# mbed_RevB.net
KiCad netlist of a schematic drawn in EAGLE
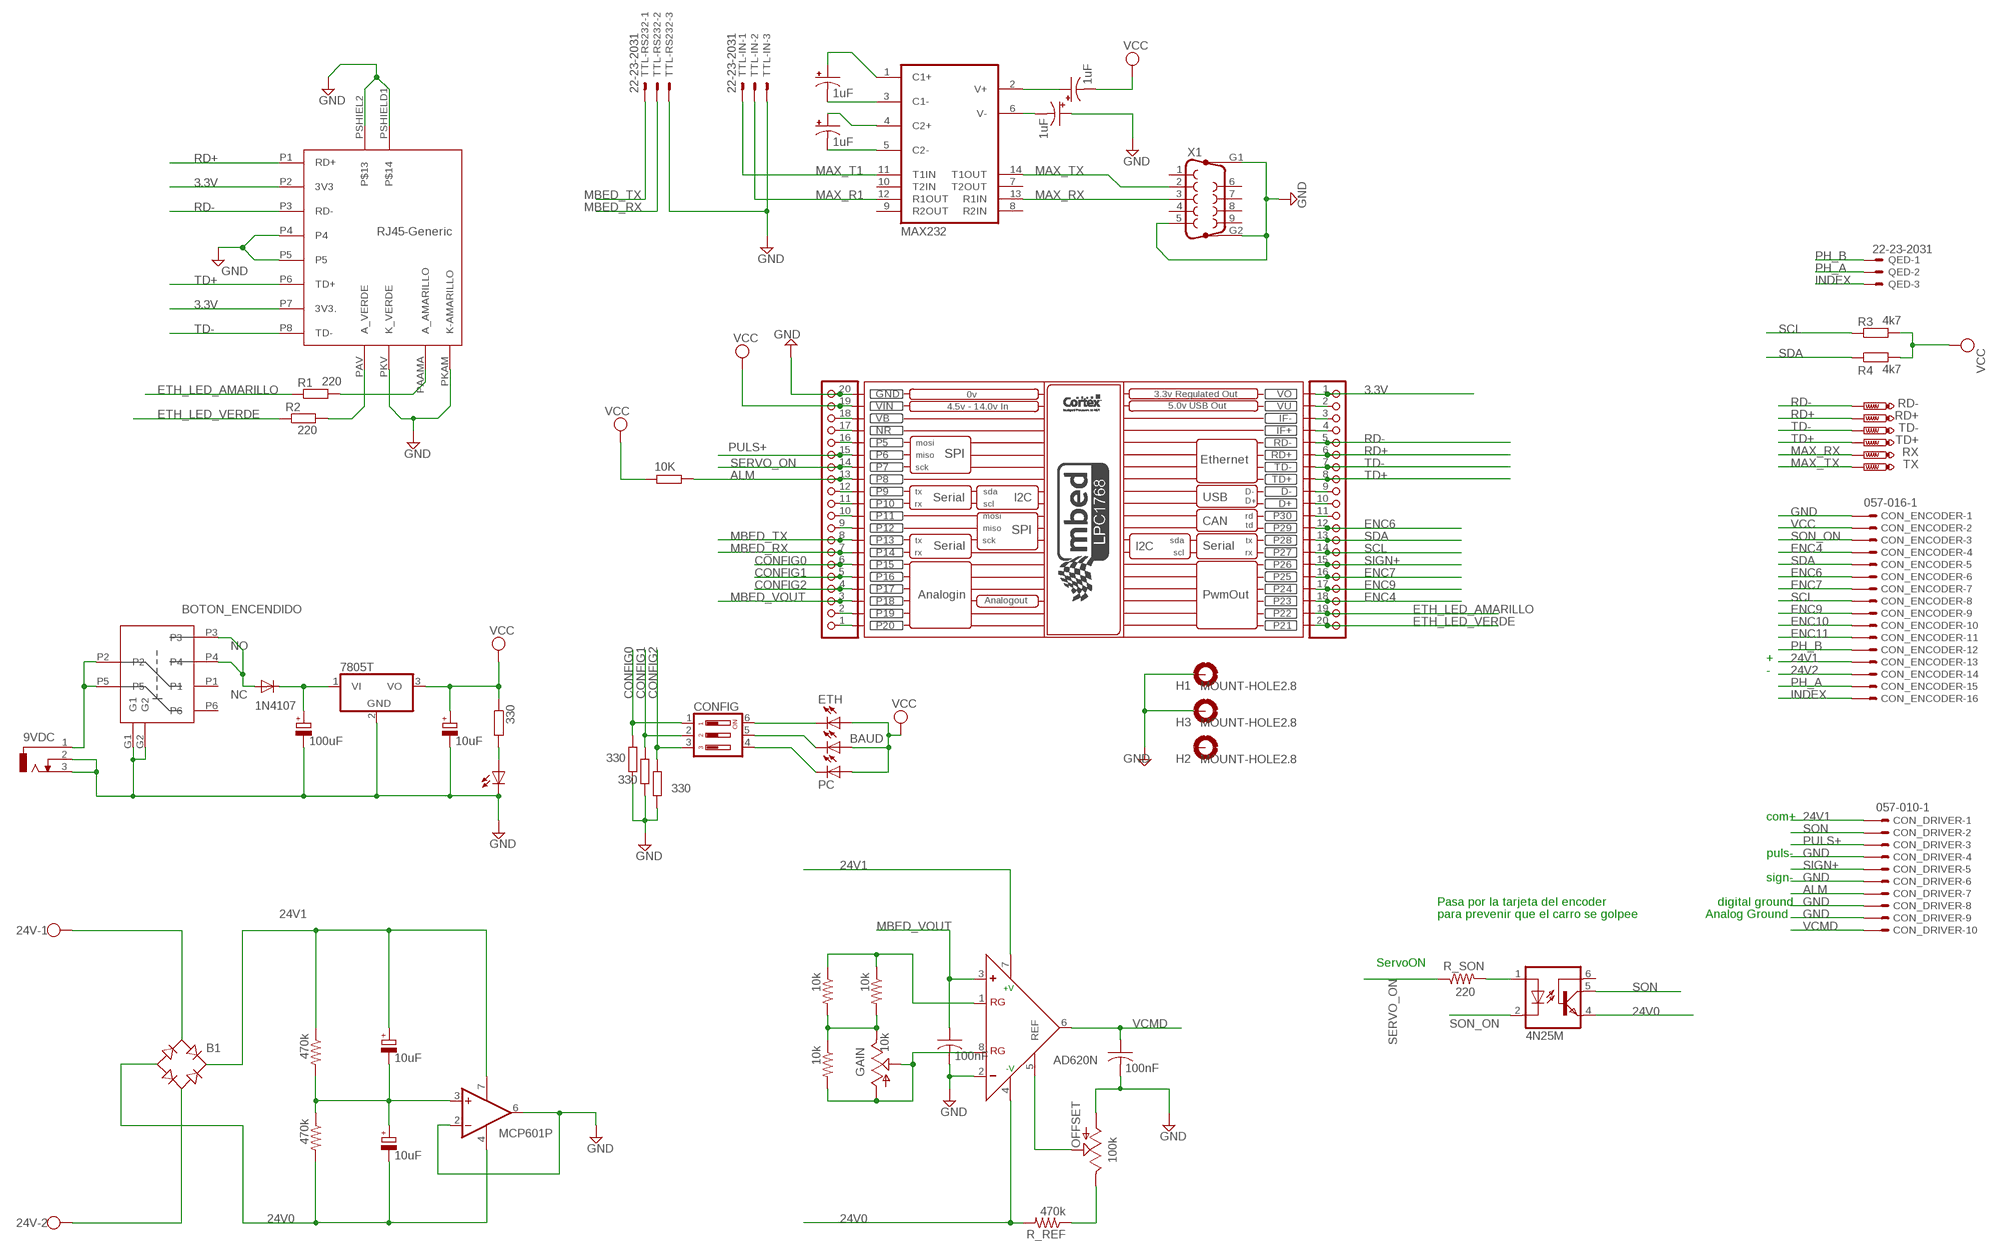
[diagram p0: schematic, sheet 1]

(export (version "E")
  (design (tool "Eeschema 10.0.6"))
  (components
    (comp (ref "9VDC")
      (value "DCJ0303")
      (footprint "eagle-import:DCJ0303")
      (libsource (lib "eagle-import") (part "DCJ0303"))
    )
    (comp (ref "24V")
      (value "W237-02P")
      (footprint "eagle-import:W237-132")
      (libsource (lib "eagle-import") (part "W237-02P"))
    )
    (comp (ref "B1")
      (value "RB1A")
      (footprint "eagle-import:RB1A")
      (libsource (lib "eagle-import") (part "RB1A"))
    )
    (comp (ref "BAUD")
      (value "LED3MM")
      (footprint "eagle-import:LED3MM")
      (libsource (lib "eagle-import") (part "LED3MM"))
    )
    (comp (ref "C1_+24")
      (value "10uF")
      (footprint "eagle-import:TT5D7")
      (libsource (lib "eagle-import") (part "CPOL-EUTT5D7"))
    )
    (comp (ref "C1_9V")
      (value "100uF")
      (footprint "eagle-import:TT5D7")
      (libsource (lib "eagle-import") (part "CPOL-EUTT5D7"))
    )
    (comp (ref "C1_MAX")
      (value "1uF")
      (footprint "eagle-import:E2,5-6E")
      (libsource (lib "eagle-import") (part "CPOL-USE2,5-6E"))
    )
    (comp (ref "C2_0V")
      (value "10uF")
      (footprint "eagle-import:TT5D7")
      (libsource (lib "eagle-import") (part "CPOL-EUTT5D7"))
    )
    (comp (ref "C2_9V")
      (value "10uF")
      (footprint "eagle-import:TT5D7")
      (libsource (lib "eagle-import") (part "CPOL-EUTT5D7"))
    )
    (comp (ref "C2_MAX")
      (value "1uF")
      (footprint "eagle-import:E2,5-6E")
      (libsource (lib "eagle-import") (part "CPOL-USE2,5-6E"))
    )
    (comp (ref "C3_AOUT")
      (value "100nF")
      (footprint "eagle-import:C025-024X044")
      (libsource (lib "eagle-import") (part "C-US025-024X044"))
    )
    (comp (ref "C3_MAX")
      (value "1uF")
      (footprint "eagle-import:E2,5-6E")
      (libsource (lib "eagle-import") (part "CPOL-USE2,5-6E"))
    )
    (comp (ref "C4_MAX")
      (value "1uF")
      (footprint "eagle-import:E2,5-6E")
      (libsource (lib "eagle-import") (part "CPOL-USE2,5-6E"))
    )
    (comp (ref "C5_AOUT")
      (value "100nF")
      (footprint "eagle-import:C025-024X044")
      (libsource (lib "eagle-import") (part "C-US025-024X044"))
    )
    (comp (ref "CONFIG")
      (value "DIP03YL")
      (footprint "eagle-import:DIP03YL")
      (libsource (lib "eagle-import") (part "DIP03YL"))
    )
    (comp (ref "CON_DRIVER")
      (value "057-010-1")
      (footprint "eagle-import:057-010-1")
      (libsource (lib "eagle-import") (part "057-010-1"))
    )
    (comp (ref "CON_ENCODER")
      (value "057-016-1")
      (footprint "eagle-import:057-016-1")
      (libsource (lib "eagle-import") (part "057-016-1"))
    )
    (comp (ref "D1_INPUT")
      (value "1N4107")
      (footprint "eagle-import:DO35-10")
      (libsource (lib "eagle-import") (part "1N4148DO35-10"))
    )
    (comp (ref "ETH")
      (value "LED3MM")
      (footprint "eagle-import:LED3MM")
      (libsource (lib "eagle-import") (part "LED3MM"))
    )
    (comp (ref "GAIN")
      (value "10k")
      (footprint "eagle-import:RJ9W")
      (libsource (lib "eagle-import") (part "TRIM_US-RJ9W"))
    )
    (comp (ref "H1")
      (value "MOUNT-HOLE2.8")
      (footprint "eagle-import:3,3-PAD")
      (libsource (lib "eagle-import") (part "MOUNT-PAD-ROUND3.3"))
    )
    (comp (ref "H2")
      (value "MOUNT-HOLE2.8")
      (footprint "eagle-import:3,3-PAD")
      (libsource (lib "eagle-import") (part "MOUNT-PAD-ROUND3.3"))
    )
    (comp (ref "H3")
      (value "MOUNT-HOLE2.8")
      (footprint "eagle-import:3,3-PAD")
      (libsource (lib "eagle-import") (part "MOUNT-PAD-ROUND3.3"))
    )
    (comp (ref "IC1")
      (value "MAX232")
      (footprint "eagle-import:DIL16")
      (libsource (lib "eagle-import") (part "MAX232"))
    )
    (comp (ref "IC2")
      (value "7805T")
      (footprint "eagle-import:TO220H")
      (libsource (lib "eagle-import") (part "78T05"))
    )
    (comp (ref "IC3")
      (value "MCP601P")
      (footprint "eagle-import:DIL08")
      (libsource (lib "eagle-import") (part "MCP601P"))
    )
    (comp (ref "IC4")
      (value "AD620N")
      (footprint "eagle-import:DIL08")
      (libsource (lib "eagle-import") (part "AD620N"))
    )
    (comp (ref "JP_LEFT")
      (value "PINHD-1X20")
      (footprint "eagle-import:1X20")
      (libsource (lib "eagle-import") (part "PINHD-1X20"))
    )
    (comp (ref "JP_RIGHT")
      (value "PINHD-1X20")
      (footprint "eagle-import:1X20")
      (libsource (lib "eagle-import") (part "PINHD-1X20"))
    )
    (comp (ref "KIT1")
      (value "MBED_NXP_LPC1768")
      (footprint "eagle-import:MBED-KIT")
      (libsource (lib "eagle-import") (part "MBED_NXP_LPC1768"))
    )
    (comp (ref "OFFSET")
      (value "100k")
      (footprint "eagle-import:RJ9W")
      (libsource (lib "eagle-import") (part "TRIM_US-RJ9W"))
    )
    (comp (ref "OK1")
      (value "4N25M")
      (footprint "eagle-import:DIL06")
      (libsource (lib "eagle-import") (part "4N?M25"))
    )
    (comp (ref "ON/OFF")
      (value "BOTON_ENCENDIDO")
      (footprint "eagle-import:BOTON_ENCNEDIDO")
      (libsource (lib "eagle-import") (part "BOTON_ENCENDIDO"))
    )
    (comp (ref "PC")
      (value "LED3MM")
      (footprint "eagle-import:LED3MM")
      (libsource (lib "eagle-import") (part "LED3MM"))
    )
    (comp (ref "POWER")
      (value "LED3MM")
      (footprint "eagle-import:LED3MM")
      (libsource (lib "eagle-import") (part "LED3MM"))
    )
    (comp (ref "PWR_LED_R")
      (value "330")
      (footprint "eagle-import:0204_7")
      (libsource (lib "eagle-import") (part "R-EU_0204/7"))
    )
    (comp (ref "QED")
      (value "22-23-2031")
      (footprint "eagle-import:22-23-2031")
      (fields (field (name "MF") "MOLEX"))
      (libsource (lib "eagle-import") (part "22-23-2031"))
    )
    (comp (ref "R1")
      (value "220")
      (footprint "eagle-import:0207_15")
      (libsource (lib "eagle-import") (part "R-EU_0207/15"))
    )
    (comp (ref "R1_DIV")
      (value "470k")
      (footprint "eagle-import:0207_10")
      (libsource (lib "eagle-import") (part "resistor_R-US_0207/10"))
    )
    (comp (ref "R1_G")
      (value "10k")
      (footprint "eagle-import:0204_7")
      (libsource (lib "eagle-import") (part "resistor_R-US_0204/7"))
    )
    (comp (ref "R2")
      (value "220")
      (footprint "eagle-import:0207_15")
      (libsource (lib "eagle-import") (part "R-EU_0207/15"))
    )
    (comp (ref "R2_DIV")
      (value "470k")
      (footprint "eagle-import:0207_10")
      (libsource (lib "eagle-import") (part "resistor_R-US_0207/10"))
    )
    (comp (ref "R2_G")
      (value "10k")
      (footprint "eagle-import:0204_7")
      (libsource (lib "eagle-import") (part "resistor_R-US_0204/7"))
    )
    (comp (ref "R3")
      (value "4k7")
      (footprint "eagle-import:0204_7")
      (libsource (lib "eagle-import") (part "R-EU_0204/7"))
    )
    (comp (ref "R3_G")
      (value "10k")
      (footprint "eagle-import:0204_7")
      (libsource (lib "eagle-import") (part "resistor_R-US_0204/7"))
    )
    (comp (ref "R4")
      (value "4k7")
      (footprint "eagle-import:0204_7")
      (libsource (lib "eagle-import") (part "R-EU_0204/7"))
    )
    (comp (ref "R13")
      (value "330")
      (footprint "eagle-import:0204_7")
      (libsource (lib "eagle-import") (part "R-EU_0204/7"))
    )
    (comp (ref "R14")
      (value "330")
      (footprint "eagle-import:0204_7")
      (libsource (lib "eagle-import") (part "R-EU_0204/7"))
    )
    (comp (ref "R15")
      (value "330")
      (footprint "eagle-import:0204_7")
      (libsource (lib "eagle-import") (part "R-EU_0204/7"))
    )
    (comp (ref "R16_ALM")
      (value "10K")
      (footprint "eagle-import:0207_12")
      (libsource (lib "eagle-import") (part "R-EU_0207/12"))
    )
    (comp (ref "RD+")
      (value "PTR1PAD1-13Y")
      (footprint "eagle-import:P1-13Y")
      (libsource (lib "eagle-import") (part "PTR1PAD1-13Y"))
    )
    (comp (ref "RD-")
      (value "PTR1PAD1-13Y")
      (footprint "eagle-import:P1-13Y")
      (libsource (lib "eagle-import") (part "PTR1PAD1-13Y"))
    )
    (comp (ref "RX")
      (value "PTR1PAD1-13Y")
      (footprint "eagle-import:P1-13Y")
      (libsource (lib "eagle-import") (part "PTR1PAD1-13Y"))
    )
    (comp (ref "R_REF")
      (value "470k")
      (footprint "eagle-import:0204_7")
      (libsource (lib "eagle-import") (part "resistor_R-US_0204/7"))
    )
    (comp (ref "R_SON")
      (value "220")
      (footprint "eagle-import:0207_7")
      (libsource (lib "eagle-import") (part "R-US_0207/7"))
    )
    (comp (ref "TD+")
      (value "PTR1PAD1-13Y")
      (footprint "eagle-import:P1-13Y")
      (libsource (lib "eagle-import") (part "PTR1PAD1-13Y"))
    )
    (comp (ref "TD-")
      (value "PTR1PAD1-13Y")
      (footprint "eagle-import:P1-13Y")
      (libsource (lib "eagle-import") (part "PTR1PAD1-13Y"))
    )
    (comp (ref "TTL-IN")
      (value "22-23-2031")
      (footprint "eagle-import:22-23-2031")
      (fields (field (name "MF") "MOLEX"))
      (libsource (lib "eagle-import") (part "22-23-2031"))
    )
    (comp (ref "TTL-RS232")
      (value "22-23-2031")
      (footprint "eagle-import:22-23-2031")
      (fields (field (name "MF") "MOLEX"))
      (libsource (lib "eagle-import") (part "22-23-2031"))
    )
    (comp (ref "TX")
      (value "PTR1PAD1-13Y")
      (footprint "eagle-import:P1-13Y")
      (libsource (lib "eagle-import") (part "PTR1PAD1-13Y"))
    )
    (comp (ref "U$1")
      (value "RJ-45-GENERIC")
      (footprint "eagle-import:RJ45-GENERIC")
      (libsource (lib "eagle-import") (part "RJ-45-GENERIC"))
    )
    (comp (ref "X1")
      (value "F09HP")
      (footprint "eagle-import:F09HP")
      (libsource (lib "eagle-import") (part "F09HP"))
    )
  )
  (nets
    (net (code "1") (name "/3.3V") (class "Default")
      (node (ref "JP_RIGHT") (pin "1") (pinfunction "1_1") (pintype "passive"))
      (node (ref "KIT1") (pin "VOUT") (pinfunction "VO_VOUT") (pintype "power_in"))
      (node (ref "U$1") (pin "P2") (pinfunction "3V3_P2") (pintype "bidirectional"))
      (node (ref "U$1") (pin "P7") (pinfunction "3V3._P7") (pintype "bidirectional"))
    )
    (net (code "2") (name "/24V0") (class "Default")
      (node (ref "B1") (pin "-") (pinfunction "-_-") (pintype "passive"))
      (node (ref "C2_0V") (pin "-") (pinfunction "-_-") (pintype "passive"))
      (node (ref "IC3") (pin "4") (pinfunction "V-_4") (pintype "power_in"))
      (node (ref "IC4") (pin "4") (pinfunction "-V_4") (pintype "power_in"))
      (node (ref "OK1") (pin "4") (pinfunction "EMI_4") (pintype "passive"))
      (node (ref "R2_DIV") (pin "2") (pinfunction "2_2") (pintype "passive"))
      (node (ref "R_REF") (pin "2") (pinfunction "2_2") (pintype "passive"))
    )
    (net (code "3") (name "/24V1") (class "Default")
      (node (ref "B1") (pin "+") (pinfunction "+_+") (pintype "passive"))
      (node (ref "C1_+24") (pin "+") (pinfunction "+_+") (pintype "passive"))
      (node (ref "CON_DRIVER") (pin "1") (pinfunction "S_1") (pintype "passive"))
      (node (ref "CON_ENCODER") (pin "13") (pinfunction "S_13") (pintype "passive"))
      (node (ref "IC3") (pin "7") (pinfunction "V+_7") (pintype "power_in"))
      (node (ref "IC4") (pin "7") (pinfunction "+V_7") (pintype "power_in"))
      (node (ref "R1_DIV") (pin "1") (pinfunction "1_1") (pintype "passive"))
    )
    (net (code "4") (name "/24V2") (class "Default")
      (node (ref "CON_ENCODER") (pin "14") (pinfunction "S_14") (pintype "passive"))
    )
    (net (code "5") (name "/ALM") (class "Default")
      (node (ref "CON_DRIVER") (pin "7") (pinfunction "S_7") (pintype "passive"))
      (node (ref "JP_LEFT") (pin "13") (pinfunction "13_13") (pintype "passive"))
      (node (ref "KIT1") (pin "P$8") (pinfunction "P8_P$8") (pintype "bidirectional"))
      (node (ref "R16_ALM") (pin "1") (pinfunction "1_1") (pintype "passive"))
    )
    (net (code "6") (name "/CONFIG0") (class "Default")
      (node (ref "CONFIG") (pin "1") (pinfunction "1_1") (pintype "passive"))
      (node (ref "JP_LEFT") (pin "6") (pinfunction "6_6") (pintype "passive"))
      (node (ref "KIT1") (pin "P$15") (pinfunction "P15_P$15") (pintype "bidirectional"))
      (node (ref "R15") (pin "2") (pinfunction "2_2") (pintype "passive"))
    )
    (net (code "7") (name "/CONFIG1") (class "Default")
      (node (ref "CONFIG") (pin "2") (pinfunction "2_2") (pintype "passive"))
      (node (ref "JP_LEFT") (pin "5") (pinfunction "5_5") (pintype "passive"))
      (node (ref "KIT1") (pin "P$16") (pinfunction "P16_P$16") (pintype "bidirectional"))
      (node (ref "R14") (pin "2") (pinfunction "2_2") (pintype "passive"))
    )
    (net (code "8") (name "/CONFIG2") (class "Default")
      (node (ref "CONFIG") (pin "3") (pinfunction "3_3") (pintype "passive"))
      (node (ref "JP_LEFT") (pin "4") (pinfunction "4_4") (pintype "passive"))
      (node (ref "KIT1") (pin "P$17") (pinfunction "P17_P$17") (pintype "bidirectional"))
      (node (ref "R13") (pin "2") (pinfunction "2_2") (pintype "passive"))
    )
    (net (code "9") (name "/ENC4") (class "Default")
      (node (ref "CON_ENCODER") (pin "4") (pinfunction "S_4") (pintype "passive"))
      (node (ref "JP_RIGHT") (pin "18") (pinfunction "18_18") (pintype "passive"))
      (node (ref "KIT1") (pin "P$23") (pinfunction "P23_P$23") (pintype "bidirectional"))
    )
    (net (code "10") (name "/ENC6") (class "Default")
      (node (ref "CON_ENCODER") (pin "6") (pinfunction "S_6") (pintype "passive"))
      (node (ref "JP_RIGHT") (pin "12") (pinfunction "12_12") (pintype "passive"))
      (node (ref "KIT1") (pin "P$29") (pinfunction "P29_P$29") (pintype "bidirectional"))
    )
    (net (code "11") (name "/ENC7") (class "Default")
      (node (ref "CON_ENCODER") (pin "7") (pinfunction "S_7") (pintype "passive"))
      (node (ref "JP_RIGHT") (pin "16") (pinfunction "16_16") (pintype "passive"))
      (node (ref "KIT1") (pin "P$25") (pinfunction "P25_P$25") (pintype "bidirectional"))
    )
    (net (code "12") (name "/ENC9") (class "Default")
      (node (ref "CON_ENCODER") (pin "9") (pinfunction "S_9") (pintype "passive"))
      (node (ref "JP_RIGHT") (pin "17") (pinfunction "17_17") (pintype "passive"))
      (node (ref "KIT1") (pin "P$24") (pinfunction "P24_P$24") (pintype "bidirectional"))
    )
    (net (code "13") (name "/ENC10") (class "Default")
      (node (ref "CON_ENCODER") (pin "10") (pinfunction "S_10") (pintype "passive"))
    )
    (net (code "14") (name "/ENC11") (class "Default")
      (node (ref "CON_ENCODER") (pin "11") (pinfunction "S_11") (pintype "passive"))
    )
    (net (code "15") (name "/ETH_LED_AMARILLO") (class "Default")
      (node (ref "JP_RIGHT") (pin "19") (pinfunction "19_19") (pintype "passive"))
      (node (ref "KIT1") (pin "P$22") (pinfunction "P22_P$22") (pintype "bidirectional"))
      (node (ref "R1") (pin "1") (pinfunction "1_1") (pintype "passive"))
    )
    (net (code "16") (name "/ETH_LED_VERDE") (class "Default")
      (node (ref "JP_RIGHT") (pin "20") (pinfunction "20_20") (pintype "passive"))
      (node (ref "KIT1") (pin "P$21") (pinfunction "P21_P$21") (pintype "bidirectional"))
      (node (ref "R2") (pin "1") (pinfunction "1_1") (pintype "passive"))
    )
    (net (code "17") (name "/INDEX") (class "Default")
      (node (ref "CON_ENCODER") (pin "16") (pinfunction "S_16") (pintype "passive"))
      (node (ref "QED") (pin "3") (pinfunction "S_3") (pintype "passive"))
    )
    (net (code "18") (name "/MAX_R1") (class "Default")
      (node (ref "IC1") (pin "12") (pinfunction "R1OUT_12") (pintype "output"))
      (node (ref "TTL-IN") (pin "2") (pinfunction "S_2") (pintype "passive"))
    )
    (net (code "19") (name "/MAX_RX") (class "Default")
      (node (ref "IC1") (pin "13") (pinfunction "R1IN_13") (pintype "input"))
      (node (ref "RX") (pin "TP") (pinfunction "TP_TP") (pintype "input"))
      (node (ref "X1") (pin "3") (pinfunction "3_3") (pintype "passive"))
    )
    (net (code "20") (name "/MAX_T1") (class "Default")
      (node (ref "IC1") (pin "11") (pinfunction "T1IN_11") (pintype "input"))
      (node (ref "TTL-IN") (pin "1") (pinfunction "S_1") (pintype "passive"))
    )
    (net (code "21") (name "/MAX_TX") (class "Default")
      (node (ref "IC1") (pin "14") (pinfunction "T1OUT_14") (pintype "output"))
      (node (ref "TX") (pin "TP") (pinfunction "TP_TP") (pintype "input"))
      (node (ref "X1") (pin "2") (pinfunction "2_2") (pintype "passive"))
    )
    (net (code "22") (name "/MBED_RX") (class "Default")
      (node (ref "JP_LEFT") (pin "7") (pinfunction "7_7") (pintype "passive"))
      (node (ref "KIT1") (pin "P$14") (pinfunction "P14_P$14") (pintype "bidirectional"))
      (node (ref "TTL-RS232") (pin "2") (pinfunction "S_2") (pintype "passive"))
    )
    (net (code "23") (name "/MBED_TX") (class "Default")
      (node (ref "JP_LEFT") (pin "8") (pinfunction "8_8") (pintype "passive"))
      (node (ref "KIT1") (pin "P$13") (pinfunction "P13_P$13") (pintype "bidirectional"))
      (node (ref "TTL-RS232") (pin "1") (pinfunction "S_1") (pintype "passive"))
    )
    (net (code "24") (name "/MBED_VOUT") (class "Default")
      (node (ref "C5_AOUT") (pin "1") (pinfunction "1_1") (pintype "passive"))
      (node (ref "IC4") (pin "3") (pinfunction "+_3") (pintype "input"))
      (node (ref "JP_LEFT") (pin "3") (pinfunction "3_3") (pintype "passive"))
      (node (ref "KIT1") (pin "P$18") (pinfunction "P18_P$18") (pintype "bidirectional"))
    )
    (net (code "25") (name "/PH_A") (class "Default")
      (node (ref "CON_ENCODER") (pin "15") (pinfunction "S_15") (pintype "passive"))
      (node (ref "QED") (pin "2") (pinfunction "S_2") (pintype "passive"))
    )
    (net (code "26") (name "/PH_B") (class "Default")
      (node (ref "CON_ENCODER") (pin "12") (pinfunction "S_12") (pintype "passive"))
      (node (ref "QED") (pin "1") (pinfunction "S_1") (pintype "passive"))
    )
    (net (code "27") (name "/PULS+") (class "Default")
      (node (ref "CON_DRIVER") (pin "3") (pinfunction "S_3") (pintype "passive"))
      (node (ref "JP_LEFT") (pin "15") (pinfunction "15_15") (pintype "passive"))
      (node (ref "KIT1") (pin "P$6") (pinfunction "P6_P$6") (pintype "bidirectional"))
    )
    (net (code "28") (name "/RD+") (class "Default")
      (node (ref "JP_RIGHT") (pin "6") (pinfunction "6_6") (pintype "passive"))
      (node (ref "KIT1") (pin "RD+") (pinfunction "RD+_RD+") (pintype "bidirectional"))
      (node (ref "RD+") (pin "TP") (pinfunction "TP_TP") (pintype "input"))
      (node (ref "U$1") (pin "P1") (pinfunction "RD+_P1") (pintype "bidirectional"))
    )
    (net (code "29") (name "/RD-") (class "Default")
      (node (ref "JP_RIGHT") (pin "5") (pinfunction "5_5") (pintype "passive"))
      (node (ref "KIT1") (pin "RD-") (pinfunction "RD-_RD-") (pintype "bidirectional"))
      (node (ref "RD-") (pin "TP") (pinfunction "TP_TP") (pintype "input"))
      (node (ref "U$1") (pin "P3") (pinfunction "RD-_P3") (pintype "bidirectional"))
    )
    (net (code "30") (name "/SCL") (class "Default")
      (node (ref "CON_ENCODER") (pin "8") (pinfunction "S_8") (pintype "passive"))
      (node (ref "JP_RIGHT") (pin "14") (pinfunction "14_14") (pintype "passive"))
      (node (ref "KIT1") (pin "P$27") (pinfunction "P27_P$27") (pintype "bidirectional"))
      (node (ref "R3") (pin "1") (pinfunction "1_1") (pintype "passive"))
    )
    (net (code "31") (name "/SDA") (class "Default")
      (node (ref "CON_ENCODER") (pin "5") (pinfunction "S_5") (pintype "passive"))
      (node (ref "JP_RIGHT") (pin "13") (pinfunction "13_13") (pintype "passive"))
      (node (ref "KIT1") (pin "P$28") (pinfunction "P28_P$28") (pintype "bidirectional"))
      (node (ref "R4") (pin "1") (pinfunction "1_1") (pintype "passive"))
    )
    (net (code "32") (name "/SERVO_ON") (class "Default")
      (node (ref "JP_LEFT") (pin "14") (pinfunction "14_14") (pintype "passive"))
      (node (ref "KIT1") (pin "P$7") (pinfunction "P7_P$7") (pintype "bidirectional"))
      (node (ref "R_SON") (pin "1") (pinfunction "1_1") (pintype "passive"))
    )
    (net (code "33") (name "/SIGN+") (class "Default")
      (node (ref "CON_DRIVER") (pin "5") (pinfunction "S_5") (pintype "passive"))
      (node (ref "JP_RIGHT") (pin "15") (pinfunction "15_15") (pintype "passive"))
      (node (ref "KIT1") (pin "P$26") (pinfunction "P26_P$26") (pintype "bidirectional"))
    )
    (net (code "34") (name "/SON") (class "Default")
      (node (ref "CON_DRIVER") (pin "2") (pinfunction "S_2") (pintype "passive"))
      (node (ref "OK1") (pin "5") (pinfunction "COL_5") (pintype "passive"))
    )
    (net (code "35") (name "/SON_ON") (class "Default")
      (node (ref "CON_ENCODER") (pin "3") (pinfunction "S_3") (pintype "passive"))
      (node (ref "OK1") (pin "2") (pinfunction "C_2") (pintype "passive"))
    )
    (net (code "36") (name "/TD+") (class "Default")
      (node (ref "JP_RIGHT") (pin "8") (pinfunction "8_8") (pintype "passive"))
      (node (ref "KIT1") (pin "TD+") (pinfunction "TD+_TD+") (pintype "bidirectional"))
      (node (ref "TD+") (pin "TP") (pinfunction "TP_TP") (pintype "input"))
      (node (ref "U$1") (pin "P6") (pinfunction "TD+_P6") (pintype "bidirectional"))
    )
    (net (code "37") (name "/TD-") (class "Default")
      (node (ref "JP_RIGHT") (pin "7") (pinfunction "7_7") (pintype "passive"))
      (node (ref "KIT1") (pin "TD-") (pinfunction "TD-_TD-") (pintype "bidirectional"))
      (node (ref "TD-") (pin "TP") (pinfunction "TP_TP") (pintype "input"))
      (node (ref "U$1") (pin "P8") (pinfunction "TD-_P8") (pintype "bidirectional"))
    )
    (net (code "38") (name "/VCMD") (class "Default")
      (node (ref "C3_AOUT") (pin "1") (pinfunction "1_1") (pintype "passive"))
      (node (ref "CON_DRIVER") (pin "10") (pinfunction "S_10") (pintype "passive"))
      (node (ref "IC4") (pin "6") (pinfunction "OUT_6") (pintype "output"))
    )
    (net (code "39") (name "GND") (class "Default")
      (node (ref "9VDC") (pin "2") (pinfunction "2_2") (pintype "passive"))
      (node (ref "9VDC") (pin "3") (pinfunction "3_3") (pintype "passive"))
      (node (ref "C1_9V") (pin "-") (pinfunction "-_-") (pintype "passive"))
      (node (ref "C2_9V") (pin "-") (pinfunction "-_-") (pintype "passive"))
      (node (ref "C3_AOUT") (pin "2") (pinfunction "2_2") (pintype "passive"))
      (node (ref "C3_MAX") (pin "+") (pinfunction "+_+") (pintype "passive"))
      (node (ref "C5_AOUT") (pin "2") (pinfunction "2_2") (pintype "passive"))
      (node (ref "CON_DRIVER") (pin "4") (pinfunction "S_4") (pintype "passive"))
      (node (ref "CON_DRIVER") (pin "6") (pinfunction "S_6") (pintype "passive"))
      (node (ref "CON_DRIVER") (pin "8") (pinfunction "S_8") (pintype "passive"))
      (node (ref "CON_DRIVER") (pin "9") (pinfunction "S_9") (pintype "passive"))
      (node (ref "CON_ENCODER") (pin "1") (pinfunction "S_1") (pintype "passive"))
      (node (ref "H1") (pin "B3,3") (pinfunction "MOUNT_B3,3") (pintype "passive"))
      (node (ref "H3") (pin "B3,3") (pinfunction "MOUNT_B3,3") (pintype "passive"))
      (node (ref "IC2") (pin "2") (pinfunction "GND_2") (pintype "passive"))
      (node (ref "IC3") (pin "2") (pinfunction "-IN_2") (pintype "input"))
      (node (ref "IC3") (pin "6") (pinfunction "OUT_6") (pintype "output"))
      (node (ref "IC4") (pin "2") (pinfunction "-_2") (pintype "input"))
      (node (ref "JP_LEFT") (pin "20") (pinfunction "20_20") (pintype "passive"))
      (node (ref "KIT1") (pin "GND") (pinfunction "GND_GND") (pintype "power_in"))
      (node (ref "OFFSET") (pin "A") (pinfunction "A_A") (pintype "passive"))
      (node (ref "ON/OFF") (pin "G1") (pinfunction "G1_G1") (pintype "bidirectional"))
      (node (ref "ON/OFF") (pin "G2") (pinfunction "G2_G2") (pintype "bidirectional"))
      (node (ref "POWER") (pin "K") (pinfunction "C_K") (pintype "passive"))
      (node (ref "R13") (pin "1") (pinfunction "1_1") (pintype "passive"))
      (node (ref "R14") (pin "1") (pinfunction "1_1") (pintype "passive"))
      (node (ref "R15") (pin "1") (pinfunction "1_1") (pintype "passive"))
      (node (ref "TTL-IN") (pin "3") (pinfunction "S_3") (pintype "passive"))
      (node (ref "TTL-RS232") (pin "3") (pinfunction "S_3") (pintype "passive"))
      (node (ref "U$1") (pin "P4") (pinfunction "P4_P4") (pintype "bidirectional"))
      (node (ref "U$1") (pin "P5") (pinfunction "P5_P5") (pintype "bidirectional"))
      (node (ref "U$1") (pin "PKAM") (pinfunction "K-AMARILLO_PKAM") (pintype "bidirectional"))
      (node (ref "U$1") (pin "PKV") (pinfunction "K_VERDE_PKV") (pintype "bidirectional"))
      (node (ref "U$1") (pin "PSHIEL2") (pinfunction "P$13_PSHIEL2") (pintype "bidirectional"))
      (node (ref "U$1") (pin "PSHIELD1") (pinfunction "P$14_PSHIELD1") (pintype "bidirectional"))
      (node (ref "X1") (pin "5") (pinfunction "5_5") (pintype "passive"))
      (node (ref "X1") (pin "G1") (pinfunction "G1_G1") (pintype "passive"))
      (node (ref "X1") (pin "G2") (pinfunction "G2_G2") (pintype "passive"))
    )
    (net (code "40") (name "Net-(9VDC-Pad1)") (class "Default")
      (node (ref "9VDC") (pin "1") (pinfunction "1_1") (pintype "passive"))
      (node (ref "ON/OFF") (pin "P2") (pinfunction "P2_P2") (pintype "bidirectional"))
      (node (ref "ON/OFF") (pin "P5") (pinfunction "P5_P5") (pintype "bidirectional"))
    )
    (net (code "41") (name "Net-(24VA-KL)") (class "Default")
      (node (ref "24V") (pin "1") (pinfunction "KL_1") (pintype "passive"))
      (node (ref "B1") (pin "AC1") (pinfunction "AC1_AC1") (pintype "passive"))
    )
    (net (code "42") (name "Net-(24VB-KL)") (class "Default")
      (node (ref "24V") (pin "2") (pinfunction "KL_2") (pintype "passive"))
      (node (ref "B1") (pin "AC2") (pinfunction "AC2_AC2") (pintype "passive"))
    )
    (net (code "43") (name "Net-(BAUD-C)") (class "Default")
      (node (ref "BAUD") (pin "K") (pinfunction "C_K") (pintype "passive"))
      (node (ref "CONFIG") (pin "5") (pinfunction "5_5") (pintype "passive"))
    )
    (net (code "44") (name "Net-(D1_INPUT-PadA)") (class "Default")
      (node (ref "D1_INPUT") (pin "A") (pinfunction "A_A") (pintype "passive"))
      (node (ref "ON/OFF") (pin "P3") (pinfunction "P3_P3") (pintype "bidirectional"))
      (node (ref "ON/OFF") (pin "P4") (pinfunction "P4_P4") (pintype "bidirectional"))
    )
    (net (code "45") (name "Net-(ETH-C)") (class "Default")
      (node (ref "CONFIG") (pin "6") (pinfunction "6_6") (pintype "passive"))
      (node (ref "ETH") (pin "K") (pinfunction "C_K") (pintype "passive"))
    )
    (net (code "46") (name "Net-(GAIN-PadA)") (class "Default")
      (node (ref "GAIN") (pin "A") (pinfunction "A_A") (pintype "passive"))
      (node (ref "GAIN") (pin "S") (pinfunction "S_S") (pintype "passive"))
      (node (ref "IC4") (pin "8") (pinfunction "RG_8") (pintype "passive"))
      (node (ref "R2_G") (pin "2") (pinfunction "2_2") (pintype "passive"))
    )
    (net (code "47") (name "Net-(GAIN-PadE)") (class "Default")
      (node (ref "GAIN") (pin "E") (pinfunction "E_E") (pintype "passive"))
      (node (ref "R1_G") (pin "2") (pinfunction "2_2") (pintype "passive"))
      (node (ref "R2_G") (pin "1") (pinfunction "1_1") (pintype "passive"))
      (node (ref "R3_G") (pin "2") (pinfunction "2_2") (pintype "passive"))
    )
    (net (code "48") (name "Net-(IC1A-C1+)") (class "Default")
      (node (ref "C1_MAX") (pin "+") (pinfunction "+_+") (pintype "passive"))
      (node (ref "IC1") (pin "1") (pinfunction "C1+_1") (pintype "bidirectional"))
    )
    (net (code "49") (name "Net-(IC1A-C1-)") (class "Default")
      (node (ref "C1_MAX") (pin "-") (pinfunction "-_-") (pintype "passive"))
      (node (ref "IC1") (pin "3") (pinfunction "C1-_3") (pintype "bidirectional"))
    )
    (net (code "50") (name "Net-(IC1A-C2+)") (class "Default")
      (node (ref "C2_MAX") (pin "+") (pinfunction "+_+") (pintype "passive"))
      (node (ref "IC1") (pin "4") (pinfunction "C2+_4") (pintype "bidirectional"))
    )
    (net (code "51") (name "Net-(IC1A-C2-)") (class "Default")
      (node (ref "C2_MAX") (pin "-") (pinfunction "-_-") (pintype "passive"))
      (node (ref "IC1") (pin "5") (pinfunction "C2-_5") (pintype "bidirectional"))
    )
    (net (code "52") (name "Net-(IC1A-V+)") (class "Default")
      (node (ref "C4_MAX") (pin "+") (pinfunction "+_+") (pintype "passive"))
      (node (ref "IC1") (pin "2") (pinfunction "V+_2") (pintype "bidirectional"))
    )
    (net (code "53") (name "Net-(IC1A-V-)") (class "Default")
      (node (ref "C3_MAX") (pin "-") (pinfunction "-_-") (pintype "passive"))
      (node (ref "IC1") (pin "6") (pinfunction "V-_6") (pintype "bidirectional"))
    )
    (net (code "54") (name "Net-(IC2-VI)") (class "Default")
      (node (ref "C1_9V") (pin "+") (pinfunction "+_+") (pintype "passive"))
      (node (ref "D1_INPUT") (pin "C") (pinfunction "C_C") (pintype "passive"))
      (node (ref "IC2") (pin "1") (pinfunction "VI_1") (pintype "input"))
    )
    (net (code "55") (name "Net-(IC3-+IN)") (class "Default")
      (node (ref "C1_+24") (pin "-") (pinfunction "-_-") (pintype "passive"))
      (node (ref "C2_0V") (pin "+") (pinfunction "+_+") (pintype "passive"))
      (node (ref "IC3") (pin "3") (pinfunction "+IN_3") (pintype "input"))
      (node (ref "R1_DIV") (pin "2") (pinfunction "2_2") (pintype "passive"))
      (node (ref "R2_DIV") (pin "1") (pinfunction "1_1") (pintype "passive"))
    )
    (net (code "56") (name "Net-(IC4-REF)") (class "Default")
      (node (ref "IC4") (pin "5") (pinfunction "REF_5") (pintype "passive"))
      (node (ref "OFFSET") (pin "S") (pinfunction "S_S") (pintype "passive"))
    )
    (net (code "57") (name "Net-(IC4-RG-Pad1)") (class "Default")
      (node (ref "IC4") (pin "1") (pinfunction "RG_1") (pintype "passive"))
      (node (ref "R1_G") (pin "1") (pinfunction "1_1") (pintype "passive"))
      (node (ref "R3_G") (pin "1") (pinfunction "1_1") (pintype "passive"))
    )
    (net (code "58") (name "Net-(JP_LEFT-Pad17)") (class "Default")
      (node (ref "JP_LEFT") (pin "17") (pinfunction "17_17") (pintype "passive"))
      (node (ref "KIT1") (pin "NR") (pinfunction "NR_NR") (pintype "power_in"))
    )
    (net (code "59") (name "Net-(JP_LEFT-Pad18)") (class "Default")
      (node (ref "JP_LEFT") (pin "18") (pinfunction "18_18") (pintype "passive"))
      (node (ref "KIT1") (pin "VB") (pinfunction "VB_VB") (pintype "power_in"))
    )
    (net (code "60") (name "Net-(JP_RIGHT-Pad2)") (class "Default")
      (node (ref "JP_RIGHT") (pin "2") (pinfunction "2_2") (pintype "passive"))
      (node (ref "KIT1") (pin "VU") (pinfunction "VU_VU") (pintype "power_in"))
    )
    (net (code "61") (name "Net-(JP_RIGHT-Pad3)") (class "Default")
      (node (ref "JP_RIGHT") (pin "3") (pinfunction "3_3") (pintype "passive"))
      (node (ref "KIT1") (pin "IF-") (pinfunction "IF-_IF-") (pintype "bidirectional"))
    )
    (net (code "62") (name "Net-(JP_RIGHT-Pad4)") (class "Default")
      (node (ref "JP_RIGHT") (pin "4") (pinfunction "4_4") (pintype "passive"))
      (node (ref "KIT1") (pin "IF+") (pinfunction "IF+_IF+") (pintype "bidirectional"))
    )
    (net (code "63") (name "Net-(JP_RIGHT-Pad9)") (class "Default")
      (node (ref "JP_RIGHT") (pin "9") (pinfunction "9_9") (pintype "passive"))
      (node (ref "KIT1") (pin "D-") (pinfunction "D-_D-") (pintype "bidirectional"))
    )
    (net (code "64") (name "Net-(JP_RIGHT-Pad10)") (class "Default")
      (node (ref "JP_RIGHT") (pin "10") (pinfunction "10_10") (pintype "passive"))
      (node (ref "KIT1") (pin "D+") (pinfunction "D+_D+") (pintype "bidirectional"))
    )
    (net (code "65") (name "Net-(KIT1-P5)") (class "Default")
      (node (ref "JP_LEFT") (pin "16") (pinfunction "16_16") (pintype "passive"))
      (node (ref "KIT1") (pin "P$5") (pinfunction "P5_P$5") (pintype "bidirectional"))
    )
    (net (code "66") (name "Net-(KIT1-P9)") (class "Default")
      (node (ref "JP_LEFT") (pin "12") (pinfunction "12_12") (pintype "passive"))
      (node (ref "KIT1") (pin "P$9") (pinfunction "P9_P$9") (pintype "bidirectional"))
    )
    (net (code "67") (name "Net-(KIT1-P10)") (class "Default")
      (node (ref "JP_LEFT") (pin "11") (pinfunction "11_11") (pintype "passive"))
      (node (ref "KIT1") (pin "P$10") (pinfunction "P10_P$10") (pintype "bidirectional"))
    )
    (net (code "68") (name "Net-(KIT1-P11)") (class "Default")
      (node (ref "JP_LEFT") (pin "10") (pinfunction "10_10") (pintype "passive"))
      (node (ref "KIT1") (pin "P$11") (pinfunction "P11_P$11") (pintype "bidirectional"))
    )
    (net (code "69") (name "Net-(KIT1-P12)") (class "Default")
      (node (ref "JP_LEFT") (pin "9") (pinfunction "9_9") (pintype "passive"))
      (node (ref "KIT1") (pin "P$12") (pinfunction "P12_P$12") (pintype "bidirectional"))
    )
    (net (code "70") (name "Net-(KIT1-P19)") (class "Default")
      (node (ref "JP_LEFT") (pin "2") (pinfunction "2_2") (pintype "passive"))
      (node (ref "KIT1") (pin "P$19") (pinfunction "P19_P$19") (pintype "bidirectional"))
    )
    (net (code "71") (name "Net-(KIT1-P20)") (class "Default")
      (node (ref "JP_LEFT") (pin "1") (pinfunction "1_1") (pintype "passive"))
      (node (ref "KIT1") (pin "P$20") (pinfunction "P20_P$20") (pintype "bidirectional"))
    )
    (net (code "72") (name "Net-(KIT1-P30)") (class "Default")
      (node (ref "JP_RIGHT") (pin "11") (pinfunction "11_11") (pintype "passive"))
      (node (ref "KIT1") (pin "P$30") (pinfunction "P30_P$30") (pintype "bidirectional"))
    )
    (net (code "73") (name "Net-(OFFSET-PadE)") (class "Default")
      (node (ref "OFFSET") (pin "E") (pinfunction "E_E") (pintype "passive"))
      (node (ref "R_REF") (pin "1") (pinfunction "1_1") (pintype "passive"))
    )
    (net (code "74") (name "Net-(OK1-A)") (class "Default")
      (node (ref "OK1") (pin "1") (pinfunction "A_1") (pintype "passive"))
      (node (ref "R_SON") (pin "2") (pinfunction "2_2") (pintype "passive"))
    )
    (net (code "75") (name "Net-(PC-C)") (class "Default")
      (node (ref "CONFIG") (pin "4") (pinfunction "4_4") (pintype "passive"))
      (node (ref "PC") (pin "K") (pinfunction "C_K") (pintype "passive"))
    )
    (net (code "76") (name "Net-(POWER-PadA)") (class "Default")
      (node (ref "POWER") (pin "A") (pinfunction "A_A") (pintype "passive"))
      (node (ref "PWR_LED_R") (pin "2") (pinfunction "2_2") (pintype "passive"))
    )
    (net (code "77") (name "Net-(U$1-A_AMARILLO)") (class "Default")
      (node (ref "R1") (pin "2") (pinfunction "2_2") (pintype "passive"))
      (node (ref "U$1") (pin "PAAMA") (pinfunction "A_AMARILLO_PAAMA") (pintype "bidirectional"))
    )
    (net (code "78") (name "Net-(U$1-A_VERDE)") (class "Default")
      (node (ref "R2") (pin "2") (pinfunction "2_2") (pintype "passive"))
      (node (ref "U$1") (pin "PAV") (pinfunction "A_VERDE_PAV") (pintype "bidirectional"))
    )
    (net (code "79") (name "VCC") (class "Default")
      (node (ref "BAUD") (pin "A") (pinfunction "A_A") (pintype "passive"))
      (node (ref "C2_9V") (pin "+") (pinfunction "+_+") (pintype "passive"))
      (node (ref "C4_MAX") (pin "-") (pinfunction "-_-") (pintype "passive"))
      (node (ref "CON_ENCODER") (pin "2") (pinfunction "S_2") (pintype "passive"))
      (node (ref "ETH") (pin "A") (pinfunction "A_A") (pintype "passive"))
      (node (ref "IC2") (pin "3") (pinfunction "VO_3") (pintype "passive"))
      (node (ref "JP_LEFT") (pin "19") (pinfunction "19_19") (pintype "passive"))
      (node (ref "KIT1") (pin "VIN") (pinfunction "VIN_VIN") (pintype "power_in"))
      (node (ref "PC") (pin "A") (pinfunction "A_A") (pintype "passive"))
      (node (ref "PWR_LED_R") (pin "1") (pinfunction "1_1") (pintype "passive"))
      (node (ref "R16_ALM") (pin "2") (pinfunction "2_2") (pintype "passive"))
      (node (ref "R3") (pin "2") (pinfunction "2_2") (pintype "passive"))
      (node (ref "R4") (pin "2") (pinfunction "2_2") (pintype "passive"))
    )
    (net (code "80") (name "unconnected-(H2-MOUNT-PadB3,3)") (class "Default")
      (node (ref "H2") (pin "B3,3") (pinfunction "MOUNT_B3,3") (pintype "passive"))
    )
    (net (code "81") (name "unconnected-(IC1A-R2IN-Pad8)") (class "Default")
      (node (ref "IC1") (pin "8") (pinfunction "R2IN_8") (pintype "input"))
    )
    (net (code "82") (name "unconnected-(IC1A-R2OUT-Pad9)") (class "Default")
      (node (ref "IC1") (pin "9") (pinfunction "R2OUT_9") (pintype "output"))
    )
    (net (code "83") (name "unconnected-(IC1A-T2IN-Pad10)") (class "Default")
      (node (ref "IC1") (pin "10") (pinfunction "T2IN_10") (pintype "input"))
    )
    (net (code "84") (name "unconnected-(IC1A-T2OUT-Pad7)") (class "Default")
      (node (ref "IC1") (pin "7") (pinfunction "T2OUT_7") (pintype "output"))
    )
    (net (code "85") (name "unconnected-(OK1-BAS-Pad6)") (class "Default")
      (node (ref "OK1") (pin "6") (pinfunction "BAS_6") (pintype "passive"))
    )
    (net (code "86") (name "unconnected-(ON/OFF-PadP1)") (class "Default")
      (node (ref "ON/OFF") (pin "P1") (pinfunction "P1_P1") (pintype "bidirectional"))
    )
    (net (code "87") (name "unconnected-(ON/OFF-PadP6)") (class "Default")
      (node (ref "ON/OFF") (pin "P6") (pinfunction "P6_P6") (pintype "bidirectional"))
    )
    (net (code "88") (name "unconnected-(X1-Pad1)") (class "Default")
      (node (ref "X1") (pin "1") (pinfunction "1_1") (pintype "passive"))
    )
    (net (code "89") (name "unconnected-(X1-Pad4)") (class "Default")
      (node (ref "X1") (pin "4") (pinfunction "4_4") (pintype "passive"))
    )
    (net (code "90") (name "unconnected-(X1-Pad6)") (class "Default")
      (node (ref "X1") (pin "6") (pinfunction "6_6") (pintype "passive"))
    )
    (net (code "91") (name "unconnected-(X1-Pad7)") (class "Default")
      (node (ref "X1") (pin "7") (pinfunction "7_7") (pintype "passive"))
    )
    (net (code "92") (name "unconnected-(X1-Pad8)") (class "Default")
      (node (ref "X1") (pin "8") (pinfunction "8_8") (pintype "passive"))
    )
    (net (code "93") (name "unconnected-(X1-Pad9)") (class "Default")
      (node (ref "X1") (pin "9") (pinfunction "9_9") (pintype "passive"))
    )
  )
)
